# batteryholder2S6P_revC.net
KiCad netlist of a schematic drawn in EAGLE
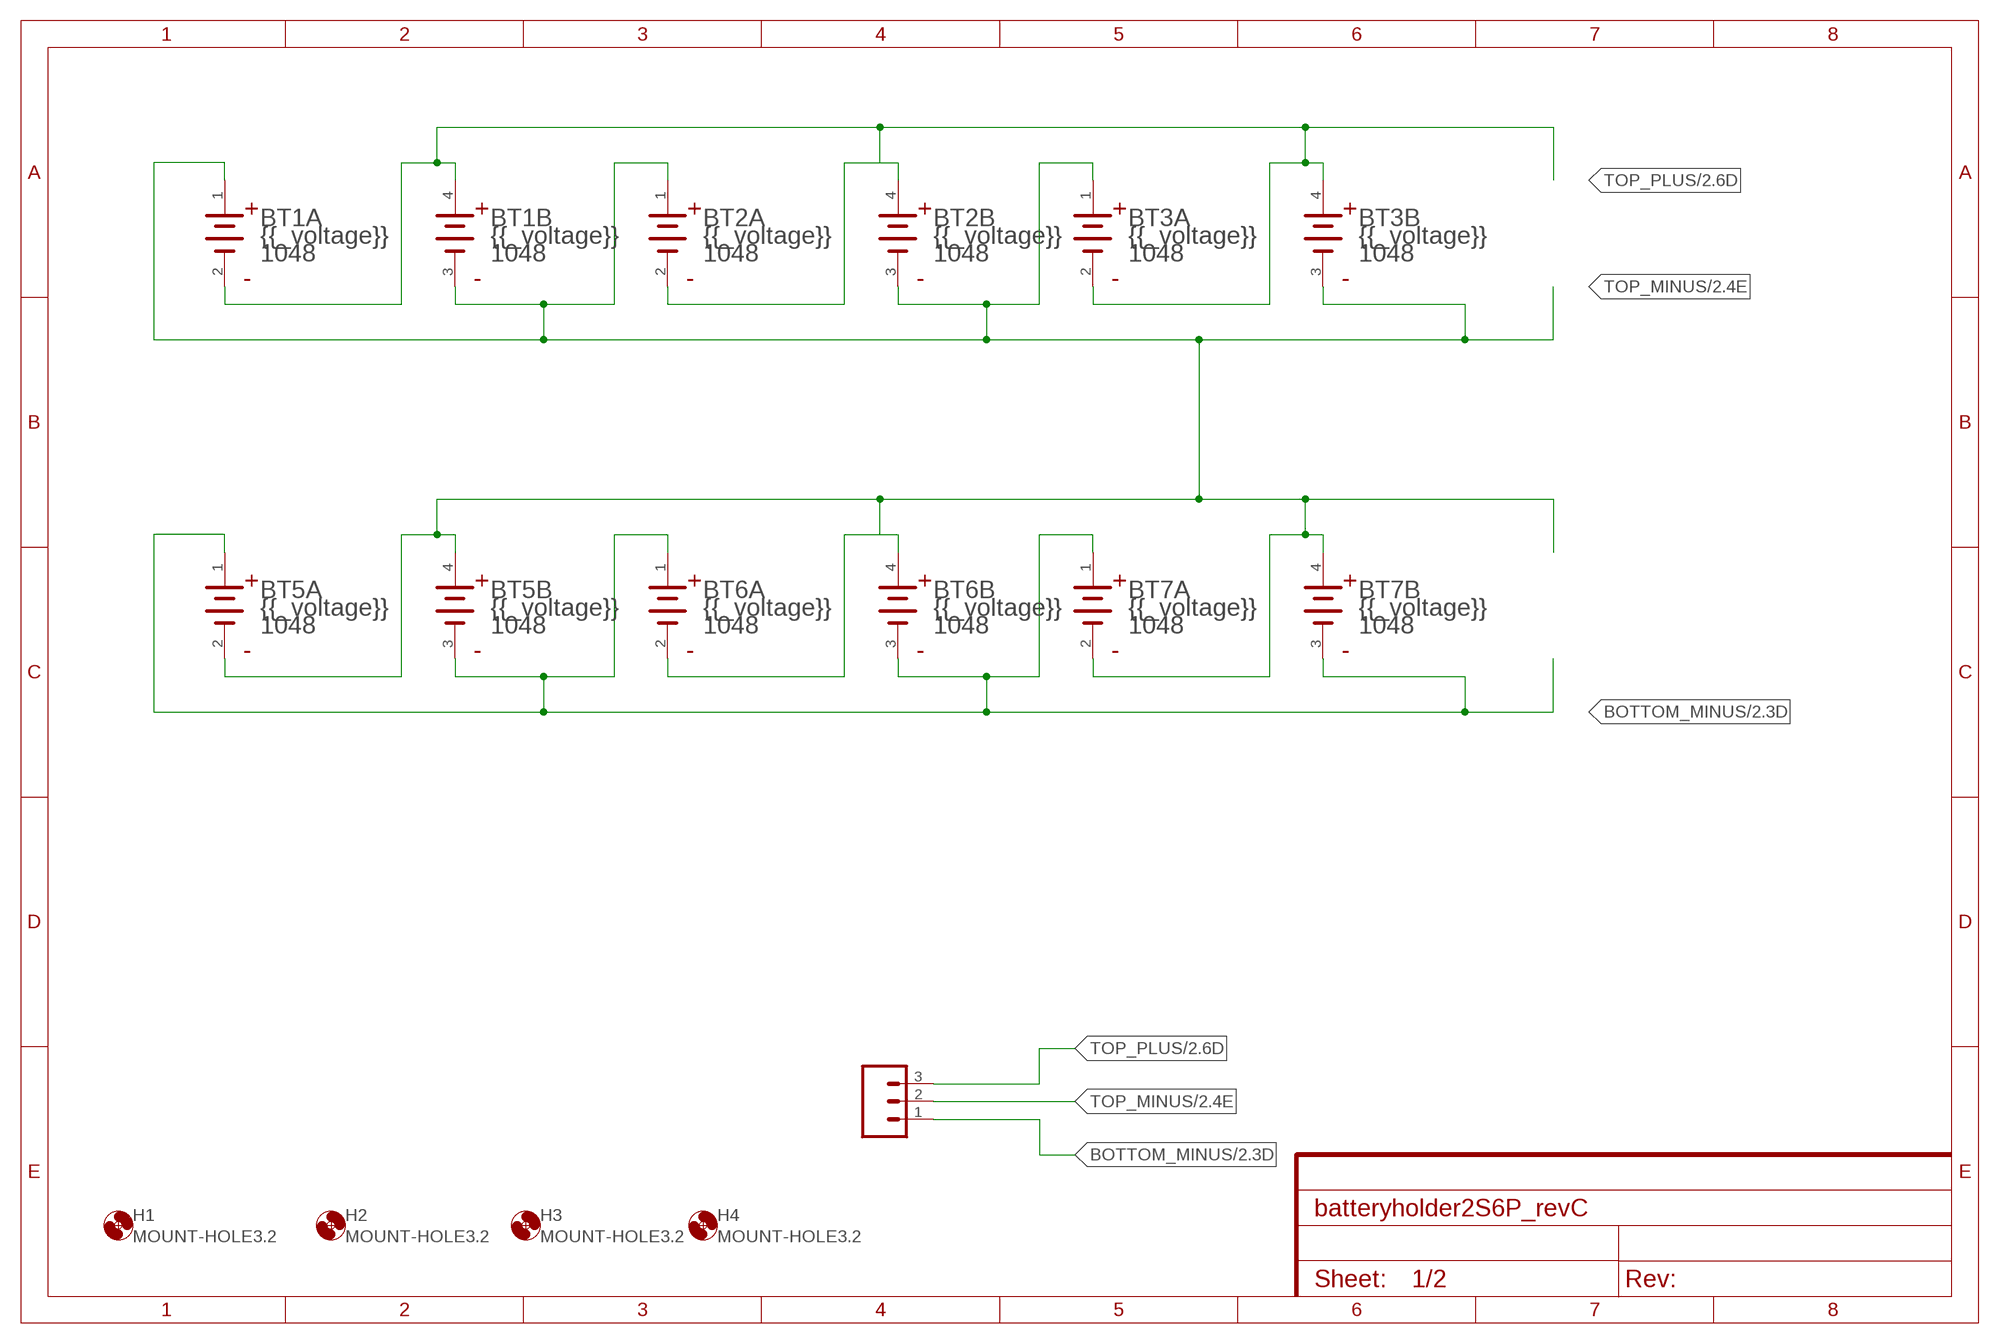
[diagram p0: schematic, sheet 1]
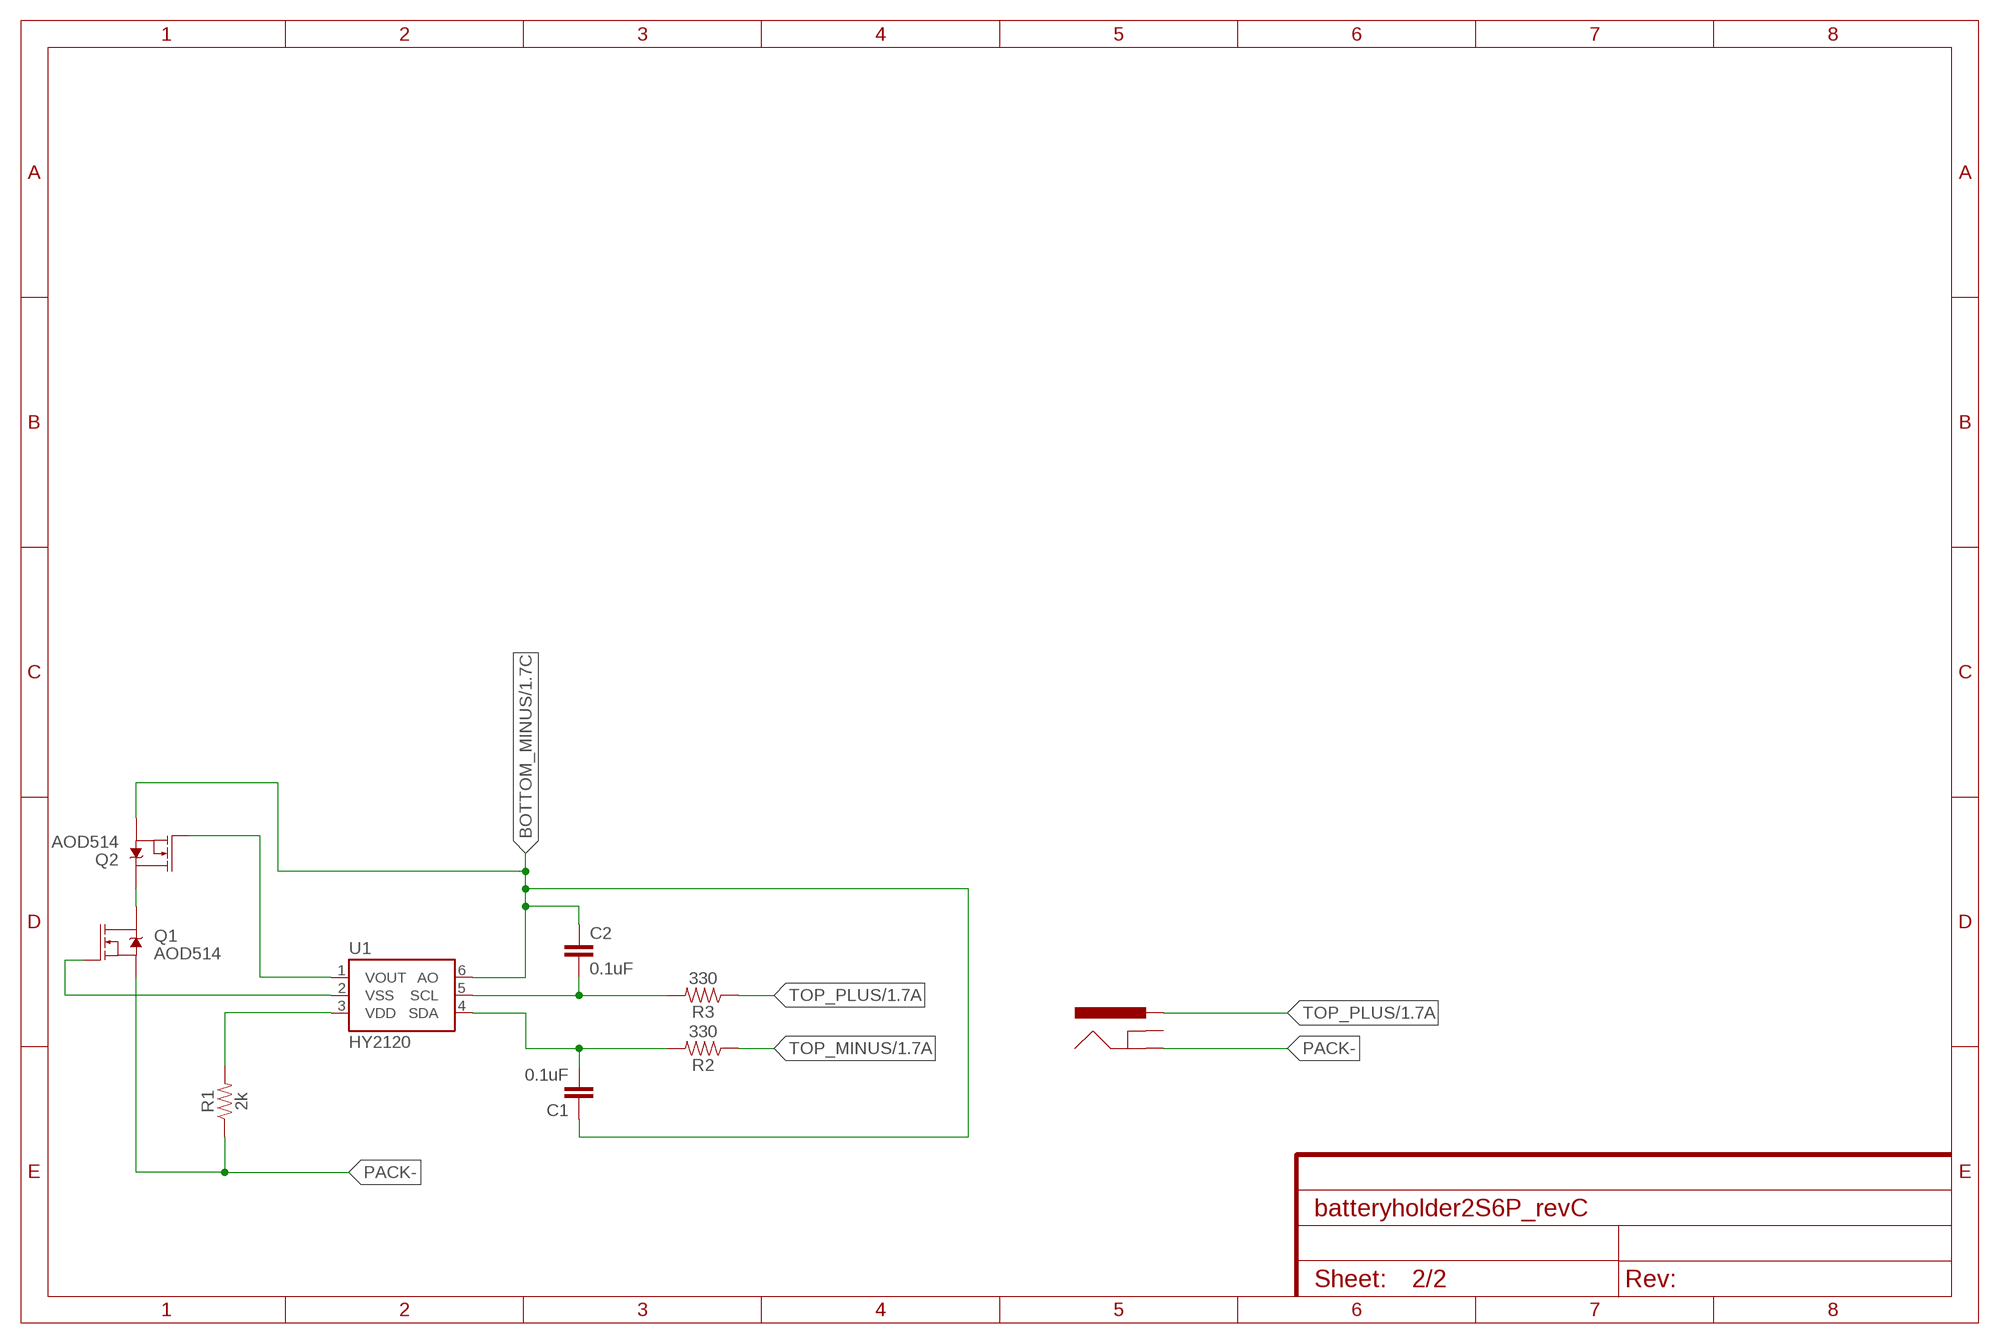
[diagram p1: schematic, sheet 2]

(export (version "E")
  (design (tool "Eeschema 10.0.6"))
  (components
    (comp (ref "C1")
      (value "0.1uF")
      (footprint "eagle-import:1206")
      (libsource (lib "eagle-import") (part "1.0UF-1206-50V-10%"))
    )
    (comp (ref "C2")
      (value "0.1uF")
      (footprint "eagle-import:1206")
      (libsource (lib "eagle-import") (part "1.0UF-1206-50V-10%"))
    )
    (comp (ref "J2")
      (value "POWER_JACKPTH_BREAD")
      (footprint "eagle-import:POWER_JACK_PTH_BREAD")
      (libsource (lib "eagle-import") (part "POWER_JACKPTH_BREAD"))
    )
    (comp (ref "Q1")
      (value "AOD514")
      (footprint "eagle-import:DPAK")
      (libsource (lib "eagle-import") (part "MOSFET-NCH-FDD8780"))
    )
    (comp (ref "Q2")
      (value "AOD514")
      (footprint "eagle-import:DPAK")
      (libsource (lib "eagle-import") (part "MOSFET-NCH-FDD8780"))
    )
    (comp (ref "R1")
      (value "2k")
      (footprint "eagle-import:1206")
      (libsource (lib "eagle-import") (part "RESISTOR1206"))
    )
    (comp (ref "R2")
      (value "330")
      (footprint "eagle-import:1206")
      (libsource (lib "eagle-import") (part "RESISTOR1206"))
    )
    (comp (ref "R3")
      (value "330")
      (footprint "eagle-import:1206")
      (libsource (lib "eagle-import") (part "RESISTOR1206"))
    )
    (comp (ref "U1")
      (value "HY2120")
      (footprint "eagle-import:SOT23-6")
      (libsource (lib "eagle-import") (part "MCP4725SOT-23"))
    )
    (comp (ref "BT1")
      (value "KEYSTONE_1048KEYSTONE_1048_0_0")
      (footprint "eagle-import:KEYSTONE_1048_0")
      (fields
        (field (name "DIGIKEY_PART_NUMBER") "36-1048-ND")
        (field (name "MF") "Keystone")
        (field (name "MOUSER_PART_NUMBER") "534-1048")
      )
      (libsource (lib "eagle-import") (part "KEYSTONE_1048KEYSTONE_1048_0_0"))
    )
    (comp (ref "BT2")
      (value "KEYSTONE_1048KEYSTONE_1048_0_0")
      (footprint "eagle-import:KEYSTONE_1048_0")
      (fields
        (field (name "DIGIKEY_PART_NUMBER") "36-1048-ND")
        (field (name "MF") "Keystone")
        (field (name "MOUSER_PART_NUMBER") "534-1048")
      )
      (libsource (lib "eagle-import") (part "KEYSTONE_1048KEYSTONE_1048_0_0"))
    )
    (comp (ref "BT3")
      (value "KEYSTONE_1048KEYSTONE_1048_0_0")
      (footprint "eagle-import:KEYSTONE_1048_0")
      (fields
        (field (name "DIGIKEY_PART_NUMBER") "36-1048-ND")
        (field (name "MF") "Keystone")
        (field (name "MOUSER_PART_NUMBER") "534-1048")
      )
      (libsource (lib "eagle-import") (part "KEYSTONE_1048KEYSTONE_1048_0_0"))
    )
    (comp (ref "BT5")
      (value "KEYSTONE_1048KEYSTONE_1048_0_0")
      (footprint "eagle-import:KEYSTONE_1048_0")
      (fields
        (field (name "DIGIKEY_PART_NUMBER") "36-1048-ND")
        (field (name "MF") "Keystone")
        (field (name "MOUSER_PART_NUMBER") "534-1048")
      )
      (libsource (lib "eagle-import") (part "KEYSTONE_1048KEYSTONE_1048_0_0"))
    )
    (comp (ref "BT6")
      (value "KEYSTONE_1048KEYSTONE_1048_0_0")
      (footprint "eagle-import:KEYSTONE_1048_0")
      (fields
        (field (name "DIGIKEY_PART_NUMBER") "36-1048-ND")
        (field (name "MF") "Keystone")
        (field (name "MOUSER_PART_NUMBER") "534-1048")
      )
      (libsource (lib "eagle-import") (part "KEYSTONE_1048KEYSTONE_1048_0_0"))
    )
    (comp (ref "BT7")
      (value "KEYSTONE_1048KEYSTONE_1048_0_0")
      (footprint "eagle-import:KEYSTONE_1048_0")
      (fields
        (field (name "DIGIKEY_PART_NUMBER") "36-1048-ND")
        (field (name "MF") "Keystone")
        (field (name "MOUSER_PART_NUMBER") "534-1048")
      )
      (libsource (lib "eagle-import") (part "KEYSTONE_1048KEYSTONE_1048_0_0"))
    )
    (comp (ref "H1")
      (value "MOUNT-HOLE3.2")
      (footprint "eagle-import:3,2")
      (libsource (lib "eagle-import") (part "MOUNT-HOLE3.2"))
    )
    (comp (ref "H2")
      (value "MOUNT-HOLE3.2")
      (footprint "eagle-import:3,2")
      (libsource (lib "eagle-import") (part "MOUNT-HOLE3.2"))
    )
    (comp (ref "H3")
      (value "MOUNT-HOLE3.2")
      (footprint "eagle-import:3,2")
      (libsource (lib "eagle-import") (part "MOUNT-HOLE3.2"))
    )
    (comp (ref "H4")
      (value "MOUNT-HOLE3.2")
      (footprint "eagle-import:3,2")
      (libsource (lib "eagle-import") (part "MOUNT-HOLE3.2"))
    )
    (comp (ref "J1")
      (value "CONN_03-SCREW-5MM")
      (footprint "eagle-import:SCREWTERMINAL-5MM-3")
      (libsource (lib "eagle-import") (part "CONN_03-SCREW-5MM"))
    )
  )
  (nets
    (net (code "1") (name "BOTTOM_MINUS") (class "Default")
      (node (ref "BT5") (pin "1") (pinfunction "1_ANODE_1") (pintype "passive"))
      (node (ref "BT5") (pin "3") (pinfunction "2_CATHODE_3") (pintype "passive"))
      (node (ref "BT6") (pin "1") (pinfunction "1_ANODE_1") (pintype "passive"))
      (node (ref "BT6") (pin "3") (pinfunction "2_CATHODE_3") (pintype "passive"))
      (node (ref "BT7") (pin "1") (pinfunction "1_ANODE_1") (pintype "passive"))
      (node (ref "BT7") (pin "3") (pinfunction "2_CATHODE_3") (pintype "passive"))
      (node (ref "C1") (pin "1") (pinfunction "1_1") (pintype "passive"))
      (node (ref "C2") (pin "1") (pinfunction "1_1") (pintype "passive"))
      (node (ref "J1") (pin "1") (pinfunction "1_1") (pintype "passive"))
      (node (ref "Q2") (pin "3") (pinfunction "S_3") (pintype "bidirectional"))
      (node (ref "U1") (pin "6") (pinfunction "AO_6") (pintype "bidirectional"))
    )
    (net (code "2") (name "Net-(Q1-D)") (class "Default")
      (node (ref "Q1") (pin "4") (pinfunction "D_4") (pintype "bidirectional"))
      (node (ref "Q2") (pin "4") (pinfunction "D_4") (pintype "bidirectional"))
    )
    (net (code "3") (name "Net-(Q1-G)") (class "Default")
      (node (ref "Q1") (pin "1") (pinfunction "G_1") (pintype "bidirectional"))
      (node (ref "U1") (pin "2") (pinfunction "VSS_2") (pintype "bidirectional"))
    )
    (net (code "4") (name "Net-(Q2-G)") (class "Default")
      (node (ref "Q2") (pin "1") (pinfunction "G_1") (pintype "bidirectional"))
      (node (ref "U1") (pin "1") (pinfunction "VOUT_1") (pintype "bidirectional"))
    )
    (net (code "5") (name "Net-(U1-SCL)") (class "Default")
      (node (ref "C2") (pin "2") (pinfunction "2_2") (pintype "passive"))
      (node (ref "R3") (pin "2") (pinfunction "2_2") (pintype "passive"))
      (node (ref "U1") (pin "5") (pinfunction "SCL_5") (pintype "bidirectional"))
    )
    (net (code "6") (name "Net-(U1-SDA)") (class "Default")
      (node (ref "C1") (pin "2") (pinfunction "2_2") (pintype "passive"))
      (node (ref "R2") (pin "2") (pinfunction "2_2") (pintype "passive"))
      (node (ref "U1") (pin "4") (pinfunction "SDA_4") (pintype "bidirectional"))
    )
    (net (code "7") (name "Net-(U1-VDD)") (class "Default")
      (node (ref "R1") (pin "2") (pinfunction "2_2") (pintype "passive"))
      (node (ref "U1") (pin "3") (pinfunction "VDD_3") (pintype "bidirectional"))
    )
    (net (code "8") (name "PACK-") (class "Default")
      (node (ref "J2") (pin "GND") (pinfunction "GND_GND") (pintype "bidirectional"))
      (node (ref "Q1") (pin "3") (pinfunction "S_3") (pintype "bidirectional"))
      (node (ref "R1") (pin "1") (pinfunction "1_1") (pintype "passive"))
    )
    (net (code "9") (name "TOP_MINUS") (class "Default")
      (node (ref "BT1") (pin "1") (pinfunction "1_ANODE_1") (pintype "passive"))
      (node (ref "BT1") (pin "3") (pinfunction "2_CATHODE_3") (pintype "passive"))
      (node (ref "BT2") (pin "1") (pinfunction "1_ANODE_1") (pintype "passive"))
      (node (ref "BT2") (pin "3") (pinfunction "2_CATHODE_3") (pintype "passive"))
      (node (ref "BT3") (pin "1") (pinfunction "1_ANODE_1") (pintype "passive"))
      (node (ref "BT3") (pin "3") (pinfunction "2_CATHODE_3") (pintype "passive"))
      (node (ref "BT5") (pin "2") (pinfunction "1_CATHODE_2") (pintype "passive"))
      (node (ref "BT5") (pin "4") (pinfunction "2_ANODE_4") (pintype "passive"))
      (node (ref "BT6") (pin "2") (pinfunction "1_CATHODE_2") (pintype "passive"))
      (node (ref "BT6") (pin "4") (pinfunction "2_ANODE_4") (pintype "passive"))
      (node (ref "BT7") (pin "2") (pinfunction "1_CATHODE_2") (pintype "passive"))
      (node (ref "BT7") (pin "4") (pinfunction "2_ANODE_4") (pintype "passive"))
      (node (ref "J1") (pin "2") (pinfunction "2_2") (pintype "passive"))
      (node (ref "R2") (pin "1") (pinfunction "1_1") (pintype "passive"))
    )
    (net (code "10") (name "TOP_PLUS") (class "Default")
      (node (ref "BT1") (pin "2") (pinfunction "1_CATHODE_2") (pintype "passive"))
      (node (ref "BT1") (pin "4") (pinfunction "2_ANODE_4") (pintype "passive"))
      (node (ref "BT2") (pin "2") (pinfunction "1_CATHODE_2") (pintype "passive"))
      (node (ref "BT2") (pin "4") (pinfunction "2_ANODE_4") (pintype "passive"))
      (node (ref "BT3") (pin "2") (pinfunction "1_CATHODE_2") (pintype "passive"))
      (node (ref "BT3") (pin "4") (pinfunction "2_ANODE_4") (pintype "passive"))
      (node (ref "J1") (pin "3") (pinfunction "3_3") (pintype "passive"))
      (node (ref "J2") (pin "PWR") (pinfunction "PWR_PWR") (pintype "bidirectional"))
      (node (ref "R3") (pin "1") (pinfunction "1_1") (pintype "passive"))
    )
    (net (code "11") (name "unconnected-(J2-PadGNDBREAK)") (class "Default")
      (node (ref "J2") (pin "GNDBREAK") (pinfunction "GNDBREAK_GNDBREAK") (pintype "bidirectional"))
    )
  )
)
